# sc16is752.net
KiCad netlist of a schematic drawn in Altium Designer
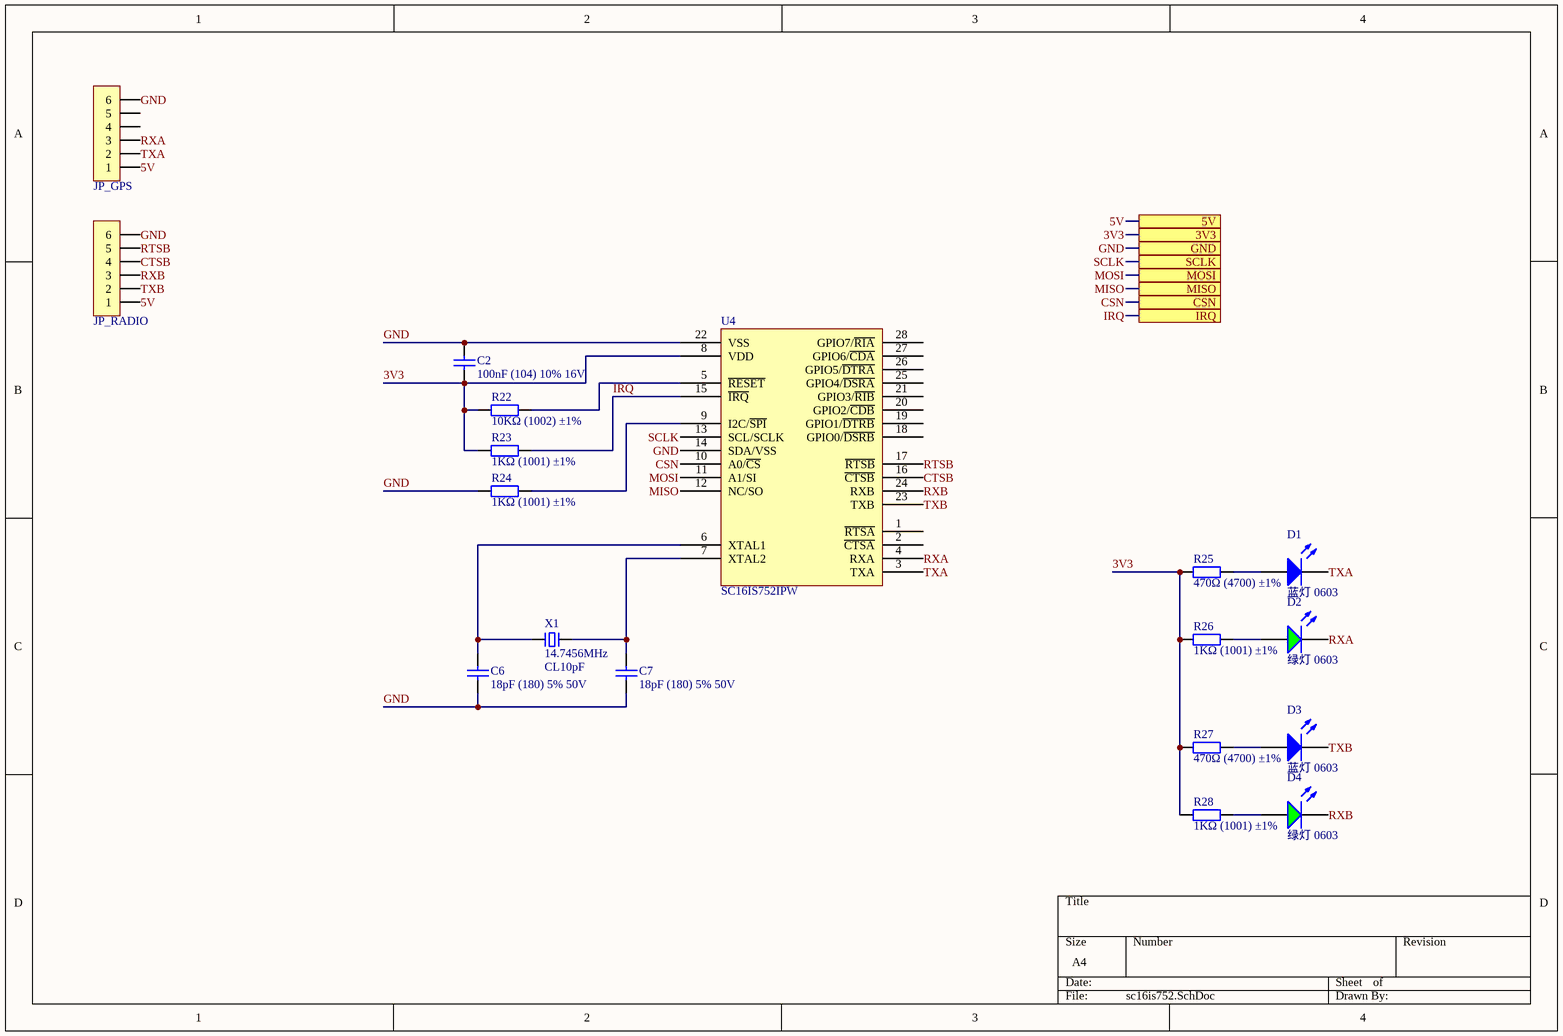
[diagram p0: sc16is752.SchDoc]

(export (version "E")
  (design (tool "Eeschema 10.0.6"))
  (components
    (comp (ref "C2")
      (value "100nF (104) 10% 16V")
      (footprint "0402_C")
      (description "贴片电容")
      (libsource (lib "Miscellaneous Devices LC") (part "0402 100nF (104) 10% 16V"))
    )
    (comp (ref "C6")
      (value "18pF (180) 5% 50V")
      (footprint "0402_C")
      (description "贴片电容")
      (libsource (lib "Miscellaneous Devices LC") (part "0402 18pF (180) 5% 50V"))
    )
    (comp (ref "C7")
      (value "18pF (180) 5% 50V")
      (footprint "0402_C")
      (description "贴片电容")
      (libsource (lib "Miscellaneous Devices LC") (part "0402 18pF (180) 5% 50V"))
    )
    (comp (ref "D1")
      (value "蓝灯 0603")
      (footprint "0603_LED_S1")
      (description "发光二极管")
      (libsource (lib "Miscellaneous Devices LC") (part "0603 蓝灯"))
    )
    (comp (ref "D2")
      (value "绿灯 0603")
      (footprint "0603_LED_S1")
      (description "发光二极管")
      (libsource (lib "Miscellaneous Devices LC") (part "0603 绿灯"))
    )
    (comp (ref "D3")
      (value "蓝灯 0603")
      (footprint "0603_LED_S1")
      (description "发光二极管")
      (libsource (lib "Miscellaneous Devices LC") (part "0603 蓝灯"))
    )
    (comp (ref "D4")
      (value "绿灯 0603")
      (footprint "0603_LED_S1")
      (description "发光二极管")
      (libsource (lib "Miscellaneous Devices LC") (part "0603 绿灯"))
    )
    (comp (ref "JP_GPS")
      (value "HDR-1X6")
      (footprint "MX 1.25-WS-6P")
      (description "6P接插件")
      (fields (field (name "版权归属") "源创客"))
      (libsource (lib "4.2   - 接插件-脚距1.25") (part "Header 6"))
    )
    (comp (ref "JP_RADIO")
      (value "HDR-1X6")
      (footprint "MX 1.25-WS-6P")
      (description "6P接插件")
      (fields (field (name "版权归属") "源创客"))
      (libsource (lib "4.2   - 接插件-脚距1.25") (part "Header 6"))
    )
    (comp (ref "R22")
      (value "10KΩ (1002) ±1%")
      (footprint "0402_R")
      (description "贴片电阻")
      (libsource (lib "Miscellaneous Devices LC") (part "0402 10KΩ (1002) 1%"))
    )
    (comp (ref "R23")
      (value "1KΩ (1001) ±1%")
      (footprint "0402_R")
      (description "贴片电阻")
      (libsource (lib "Miscellaneous Devices LC") (part "0402 1KΩ (1001) 1%"))
    )
    (comp (ref "R24")
      (value "1KΩ (1001) ±1%")
      (footprint "0402_R")
      (description "贴片电阻")
      (libsource (lib "Miscellaneous Devices LC") (part "0402 1KΩ (1001) 1%"))
    )
    (comp (ref "R25")
      (value "470Ω (4700) ±1%")
      (footprint "0402_R")
      (description "贴片电阻")
      (libsource (lib "Miscellaneous Devices LC") (part "0402 470Ω (4700) 1%"))
    )
    (comp (ref "R26")
      (value "1KΩ (1001) ±1%")
      (footprint "0402_R")
      (description "贴片电阻")
      (libsource (lib "Miscellaneous Devices LC") (part "0402 1KΩ (1001) 1%"))
    )
    (comp (ref "R27")
      (value "470Ω (4700) ±1%")
      (footprint "0402_R")
      (description "贴片电阻")
      (libsource (lib "Miscellaneous Devices LC") (part "0402 470Ω (4700) 1%"))
    )
    (comp (ref "R28")
      (value "1KΩ (1001) ±1%")
      (footprint "0402_R")
      (description "贴片电阻")
      (libsource (lib "Miscellaneous Devices LC") (part "0402 1KΩ (1001) 1%"))
    )
    (comp (ref "U4")
      (value "SC16IS752IPW")
      (footprint "TSSOP28_n")
      (libsource (lib "SC16IS752_SC16IS762") (part "SC16IS752IPW"))
    )
    (comp (ref "X1")
      (value "14.7456MHz")
      (footprint "OSC HC-49SMD")
      (description "2脚无源脚晶振")
      (fields (field (name "负载电容") "CL10pF") (field (name "版权归属") "源创客"))
      (libsource (lib "10.1 - 保险丝-晶振") (part "XTAL-2P"))
    )
  )
  (nets
    (net (code "1") (name "/3V3") (class "Default")
      (node (ref "C2") (pin "1") (pinfunction "1_1") (pintype "passive"))
      (node (ref "R22") (pin "1") (pinfunction "1_1") (pintype "passive"))
      (node (ref "R23") (pin "1") (pinfunction "1_1") (pintype "passive"))
      (node (ref "R25") (pin "1") (pinfunction "1_1") (pintype "passive"))
      (node (ref "R26") (pin "1") (pinfunction "1_1") (pintype "passive"))
      (node (ref "R27") (pin "1") (pinfunction "1_1") (pintype "passive"))
      (node (ref "R28") (pin "1") (pinfunction "1_1") (pintype "passive"))
      (node (ref "U4") (pin "8") (pinfunction "VDD_8") (pintype "passive"))
    )
    (net (code "2") (name "/5V") (class "Default")
      (node (ref "JP_GPS") (pin "1") (pinfunction "1_1") (pintype "passive"))
      (node (ref "JP_RADIO") (pin "1") (pinfunction "1_1") (pintype "passive"))
    )
    (net (code "3") (name "/CSN") (class "Default")
      (node (ref "U4") (pin "10") (pinfunction "A0/~{CS}_10") (pintype "passive"))
    )
    (net (code "4") (name "/CTSB") (class "Default")
      (node (ref "JP_RADIO") (pin "4") (pinfunction "4_4") (pintype "passive"))
      (node (ref "U4") (pin "16") (pinfunction "~{CTSB}_16") (pintype "passive"))
    )
    (net (code "5") (name "/GND") (class "Default")
      (node (ref "C2") (pin "2") (pinfunction "2_2") (pintype "passive"))
      (node (ref "C6") (pin "1") (pinfunction "1_1") (pintype "passive"))
      (node (ref "C7") (pin "1") (pinfunction "1_1") (pintype "passive"))
      (node (ref "JP_GPS") (pin "6") (pinfunction "6_6") (pintype "passive"))
      (node (ref "JP_RADIO") (pin "6") (pinfunction "6_6") (pintype "passive"))
      (node (ref "R24") (pin "1") (pinfunction "1_1") (pintype "passive"))
      (node (ref "U4") (pin "14") (pinfunction "SDA/VSS_14") (pintype "passive"))
      (node (ref "U4") (pin "22") (pinfunction "VSS_22") (pintype "passive"))
    )
    (net (code "6") (name "/IRQ") (class "Default")
      (node (ref "R23") (pin "2") (pinfunction "2_2") (pintype "passive"))
      (node (ref "U4") (pin "15") (pinfunction "~{IRQ}_15") (pintype "passive"))
    )
    (net (code "7") (name "/MISO") (class "Default")
      (node (ref "U4") (pin "12") (pinfunction "NC/SO_12") (pintype "passive"))
    )
    (net (code "8") (name "/MOSI") (class "Default")
      (node (ref "U4") (pin "11") (pinfunction "A1/SI_11") (pintype "passive"))
    )
    (net (code "9") (name "/RTSB") (class "Default")
      (node (ref "JP_RADIO") (pin "5") (pinfunction "5_5") (pintype "passive"))
      (node (ref "U4") (pin "17") (pinfunction "~{RTSB}_17") (pintype "passive"))
    )
    (net (code "10") (name "/RXA") (class "Default")
      (node (ref "D2") (pin "K") (pinfunction "K_K") (pintype "passive"))
      (node (ref "JP_GPS") (pin "3") (pinfunction "3_3") (pintype "passive"))
      (node (ref "U4") (pin "4") (pinfunction "RXA_4") (pintype "passive"))
    )
    (net (code "11") (name "/RXB") (class "Default")
      (node (ref "D4") (pin "K") (pinfunction "K_K") (pintype "passive"))
      (node (ref "JP_RADIO") (pin "3") (pinfunction "3_3") (pintype "passive"))
      (node (ref "U4") (pin "24") (pinfunction "RXB_24") (pintype "passive"))
    )
    (net (code "12") (name "/SCLK") (class "Default")
      (node (ref "U4") (pin "13") (pinfunction "SCL/SCLK_13") (pintype "passive"))
    )
    (net (code "13") (name "/TXA") (class "Default")
      (node (ref "D1") (pin "K") (pinfunction "K_K") (pintype "passive"))
      (node (ref "JP_GPS") (pin "2") (pinfunction "2_2") (pintype "passive"))
      (node (ref "U4") (pin "3") (pinfunction "TXA_3") (pintype "passive"))
    )
    (net (code "14") (name "/TXB") (class "Default")
      (node (ref "D3") (pin "K") (pinfunction "K_K") (pintype "passive"))
      (node (ref "JP_RADIO") (pin "2") (pinfunction "2_2") (pintype "passive"))
      (node (ref "U4") (pin "23") (pinfunction "TXB_23") (pintype "passive"))
    )
    (net (code "15") (name "Net-(D1-PadA)") (class "Default")
      (node (ref "D1") (pin "A") (pinfunction "A_A") (pintype "passive"))
      (node (ref "R25") (pin "2") (pinfunction "2_2") (pintype "passive"))
    )
    (net (code "16") (name "Net-(D2-PadA)") (class "Default")
      (node (ref "D2") (pin "A") (pinfunction "A_A") (pintype "passive"))
      (node (ref "R26") (pin "2") (pinfunction "2_2") (pintype "passive"))
    )
    (net (code "17") (name "Net-(D3-PadA)") (class "Default")
      (node (ref "D3") (pin "A") (pinfunction "A_A") (pintype "passive"))
      (node (ref "R27") (pin "2") (pinfunction "2_2") (pintype "passive"))
    )
    (net (code "18") (name "Net-(D4-PadA)") (class "Default")
      (node (ref "D4") (pin "A") (pinfunction "A_A") (pintype "passive"))
      (node (ref "R28") (pin "2") (pinfunction "2_2") (pintype "passive"))
    )
    (net (code "19") (name "Net-(U4-I2C{slash}~{SPI})") (class "Default")
      (node (ref "R24") (pin "2") (pinfunction "2_2") (pintype "passive"))
      (node (ref "U4") (pin "9") (pinfunction "I2C/~{SPI}_9") (pintype "passive"))
    )
    (net (code "20") (name "Net-(U4-XTAL1)") (class "Default")
      (node (ref "C6") (pin "2") (pinfunction "2_2") (pintype "passive"))
      (node (ref "U4") (pin "6") (pinfunction "XTAL1_6") (pintype "passive"))
      (node (ref "X1") (pin "1") (pinfunction "1_1") (pintype "passive"))
    )
    (net (code "21") (name "Net-(U4-XTAL2)") (class "Default")
      (node (ref "C7") (pin "2") (pinfunction "2_2") (pintype "passive"))
      (node (ref "U4") (pin "7") (pinfunction "XTAL2_7") (pintype "passive"))
      (node (ref "X1") (pin "2") (pinfunction "2_2") (pintype "passive"))
    )
    (net (code "22") (name "Net-(U4-~{RESET})") (class "Default")
      (node (ref "R22") (pin "2") (pinfunction "2_2") (pintype "passive"))
      (node (ref "U4") (pin "5") (pinfunction "~{RESET}_5") (pintype "passive"))
    )
    (net (code "23") (name "unconnected-(JP_GPS-Pad4)") (class "Default")
      (node (ref "JP_GPS") (pin "4") (pinfunction "4_4") (pintype "passive"))
    )
    (net (code "24") (name "unconnected-(JP_GPS-Pad5)") (class "Default")
      (node (ref "JP_GPS") (pin "5") (pinfunction "5_5") (pintype "passive"))
    )
    (net (code "25") (name "unconnected-(U4-GPIO0{slash}~{DSRB}-Pad18)") (class "Default")
      (node (ref "U4") (pin "18") (pinfunction "GPIO0/~{DSRB}_18") (pintype "passive"))
    )
    (net (code "26") (name "unconnected-(U4-GPIO1{slash}~{DTRB}-Pad19)") (class "Default")
      (node (ref "U4") (pin "19") (pinfunction "GPIO1/~{DTRB}_19") (pintype "passive"))
    )
    (net (code "27") (name "unconnected-(U4-GPIO2{slash}~{CDB}-Pad20)") (class "Default")
      (node (ref "U4") (pin "20") (pinfunction "GPIO2/~{CDB}_20") (pintype "passive"))
    )
    (net (code "28") (name "unconnected-(U4-GPIO3{slash}~{RIB}-Pad21)") (class "Default")
      (node (ref "U4") (pin "21") (pinfunction "GPIO3/~{RIB}_21") (pintype "passive"))
    )
    (net (code "29") (name "unconnected-(U4-GPIO4{slash}~{DSRA}-Pad25)") (class "Default")
      (node (ref "U4") (pin "25") (pinfunction "GPIO4/~{DSRA}_25") (pintype "passive"))
    )
    (net (code "30") (name "unconnected-(U4-GPIO5{slash}~{DTRA}-Pad26)") (class "Default")
      (node (ref "U4") (pin "26") (pinfunction "GPIO5/~{DTRA}_26") (pintype "passive"))
    )
    (net (code "31") (name "unconnected-(U4-GPIO6{slash}~{CDA}-Pad27)") (class "Default")
      (node (ref "U4") (pin "27") (pinfunction "GPIO6/~{CDA}_27") (pintype "passive"))
    )
    (net (code "32") (name "unconnected-(U4-GPIO7{slash}~{RIA}-Pad28)") (class "Default")
      (node (ref "U4") (pin "28") (pinfunction "GPIO7/~{RIA}_28") (pintype "passive"))
    )
    (net (code "33") (name "unconnected-(U4-~{CTSA}-Pad2)") (class "Default")
      (node (ref "U4") (pin "2") (pinfunction "~{CTSA}_2") (pintype "passive"))
    )
    (net (code "34") (name "unconnected-(U4-~{RTSA}-Pad1)") (class "Default")
      (node (ref "U4") (pin "1") (pinfunction "~{RTSA}_1") (pintype "passive"))
    )
  )
)
